# PiHatV2.net
KiCad netlist of a schematic drawn in EAGLE
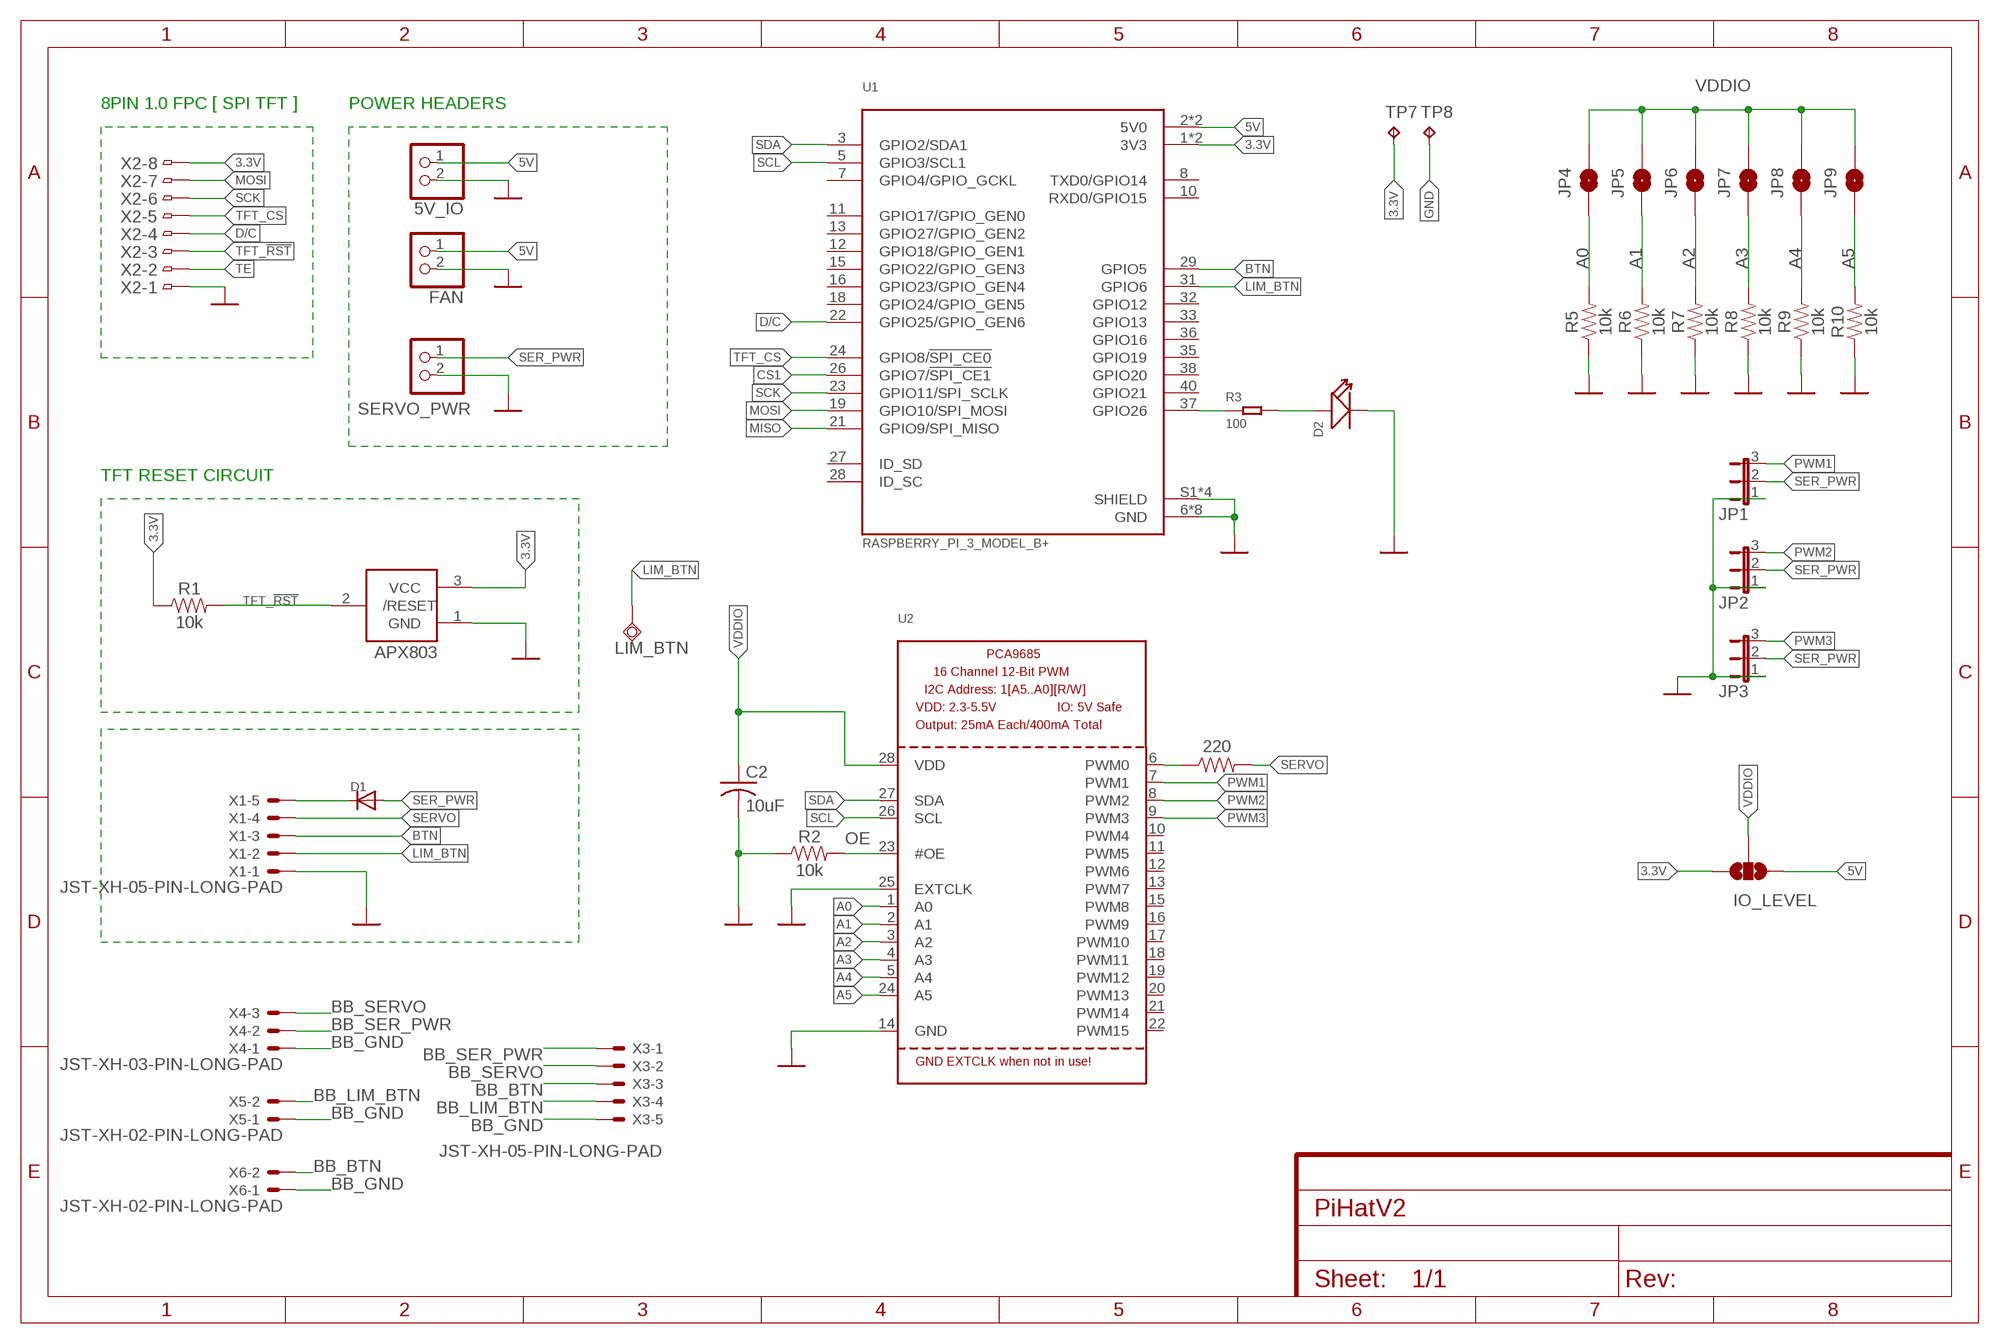
[diagram p0: schematic, sheet 1]

(export (version "E")
  (design (tool "Eeschema 10.0.6"))
  (components
    (comp (ref "5V_IO")
      (value "ONBOARDCONTROLINTERFACE_LED-BADGE_SCHEMATIC_ADAFRUIT_JST_2PIN-SMT-RA")
      (footprint "eagle-import:ONBOARDCONTROLINTERFACE_LED-BADGE_SCHEMATIC_ADAFRUIT_JST-PH-2-SMT-RA")
      (libsource (lib "eagle-import") (part "ONBOARDCONTROLINTERFACE_LED-BADGE_SCHEMATIC_ADAFRUIT_JST_2PIN-SMT-RA"))
    )
    (comp (ref "APX803")
      (value "ADAFRUIT_AXP083-SAG")
      (footprint "eagle-import:ADAFRUIT_SOT23")
      (libsource (lib "eagle-import") (part "ADAFRUIT_AXP083-SAG"))
    )
    (comp (ref "C2")
      (value "10uF")
      (footprint "eagle-import:C0805K")
      (libsource (lib "eagle-import") (part "C-USC0805K"))
    )
    (comp (ref "D1")
      (value "DIODESMA")
      (footprint "eagle-import:SMADIODE")
      (libsource (lib "eagle-import") (part "DIODESMA"))
    )
    (comp (ref "D2")
      (value "BLUE-0603")
      (footprint "eagle-import:LED-0603")
      (fields (field (name "MPN") "19-217-BHC-ZL1M2RY-3T"))
      (libsource (lib "eagle-import") (part "SMD-LED-CLEAR-BLUE(0603)"))
    )
    (comp (ref "FAN")
      (value "ONBOARDCONTROLINTERFACE_LED-BADGE_SCHEMATIC_ADAFRUIT_JST_2PIN-SMT-RA")
      (footprint "eagle-import:ONBOARDCONTROLINTERFACE_LED-BADGE_SCHEMATIC_ADAFRUIT_JST-PH-2-SMT-RA")
      (libsource (lib "eagle-import") (part "ONBOARDCONTROLINTERFACE_LED-BADGE_SCHEMATIC_ADAFRUIT_JST_2PIN-SMT-RA"))
    )
    (comp (ref "IO_LEVEL")
      (value "JUMPER-SMT_3_NO_NO-SILK")
      (footprint "eagle-import:SMT-JUMPER_3_NO_NO-SILK")
      (libsource (lib "eagle-import") (part "JUMPER-SMT_3_NO_NO-SILK"))
    )
    (comp (ref "JP1")
      (value "LED-BADGE_SCHEMATIC_JUMPER_JP2E")
      (footprint "eagle-import:LED-BADGE_SCHEMATIC_JUMPER_JP2")
      (libsource (lib "eagle-import") (part "LED-BADGE_SCHEMATIC_JUMPER_JP2E"))
    )
    (comp (ref "JP2")
      (value "LED-BADGE_SCHEMATIC_JUMPER_JP2E")
      (footprint "eagle-import:LED-BADGE_SCHEMATIC_JUMPER_JP2")
      (libsource (lib "eagle-import") (part "LED-BADGE_SCHEMATIC_JUMPER_JP2E"))
    )
    (comp (ref "JP3")
      (value "LED-BADGE_SCHEMATIC_JUMPER_JP2E")
      (footprint "eagle-import:LED-BADGE_SCHEMATIC_JUMPER_JP2")
      (libsource (lib "eagle-import") (part "LED-BADGE_SCHEMATIC_JUMPER_JP2E"))
    )
    (comp (ref "JP4")
      (value "JUMPER-SMT_2_NO_NO-SILK")
      (footprint "eagle-import:SMT-JUMPER_2_NO_NO-SILK")
      (libsource (lib "eagle-import") (part "JUMPER-SMT_2_NO_NO-SILK"))
    )
    (comp (ref "JP5")
      (value "JUMPER-SMT_2_NO_NO-SILK")
      (footprint "eagle-import:SMT-JUMPER_2_NO_NO-SILK")
      (libsource (lib "eagle-import") (part "JUMPER-SMT_2_NO_NO-SILK"))
    )
    (comp (ref "JP6")
      (value "JUMPER-SMT_2_NO_NO-SILK")
      (footprint "eagle-import:SMT-JUMPER_2_NO_NO-SILK")
      (libsource (lib "eagle-import") (part "JUMPER-SMT_2_NO_NO-SILK"))
    )
    (comp (ref "JP7")
      (value "JUMPER-SMT_2_NO_NO-SILK")
      (footprint "eagle-import:SMT-JUMPER_2_NO_NO-SILK")
      (libsource (lib "eagle-import") (part "JUMPER-SMT_2_NO_NO-SILK"))
    )
    (comp (ref "JP8")
      (value "JUMPER-SMT_2_NO_NO-SILK")
      (footprint "eagle-import:SMT-JUMPER_2_NO_NO-SILK")
      (libsource (lib "eagle-import") (part "JUMPER-SMT_2_NO_NO-SILK"))
    )
    (comp (ref "JP9")
      (value "JUMPER-SMT_2_NO_NO-SILK")
      (footprint "eagle-import:SMT-JUMPER_2_NO_NO-SILK")
      (libsource (lib "eagle-import") (part "JUMPER-SMT_2_NO_NO-SILK"))
    )
    (comp (ref "LIM_BTN")
      (value "TESTPAD_TPSQB1,27")
      (footprint "eagle-import:TESTPAD_B1,27")
      (libsource (lib "eagle-import") (part "TESTPAD_TPSQB1,27"))
    )
    (comp (ref "R1")
      (value "10k")
      (footprint "eagle-import:ARDUINO_3V_TTL_INTERFACE_2_PI_SPARKFUN-RESISTORS_0603_1")
      (libsource (lib "eagle-import") (part "ARDUINO_3V_TTL_INTERFACE_2_PI_SPARKFUN-RESISTORS_10KOHM-0603-1/10W-1%"))
    )
    (comp (ref "R2")
      (value "10k")
      (footprint "eagle-import:ARDUINO_3V_TTL_INTERFACE_2_PI_SPARKFUN-RESISTORS_0603_1")
      (libsource (lib "eagle-import") (part "ARDUINO_3V_TTL_INTERFACE_2_PI_SPARKFUN-RESISTORS_10KOHM-0603-1/10W-1%"))
    )
    (comp (ref "R3")
      (value "100")
      (footprint "eagle-import:R0805")
      (fields (field (name "MPN") "RC0805JR-071KL"))
      (libsource (lib "eagle-import") (part "SMD-RES-1K-5%-1/8W(0805)"))
    )
    (comp (ref "R4")
      (value "220")
      (footprint "eagle-import:ARDUINO_3V_TTL_INTERFACE_2_PI_SPARKFUN-RESISTORS_0603_1")
      (libsource (lib "eagle-import") (part "ARDUINO_3V_TTL_INTERFACE_2_PI_SPARKFUN-RESISTORS_10KOHM-0603-1/10W-1%"))
    )
    (comp (ref "R5")
      (value "10k")
      (footprint "eagle-import:ARDUINO_3V_TTL_INTERFACE_2_PI_SPARKFUN-RESISTORS_0603_1")
      (libsource (lib "eagle-import") (part "ARDUINO_3V_TTL_INTERFACE_2_PI_SPARKFUN-RESISTORS_10KOHM-0603-1/10W-1%"))
    )
    (comp (ref "R6")
      (value "10k")
      (footprint "eagle-import:ARDUINO_3V_TTL_INTERFACE_2_PI_SPARKFUN-RESISTORS_0603_1")
      (libsource (lib "eagle-import") (part "ARDUINO_3V_TTL_INTERFACE_2_PI_SPARKFUN-RESISTORS_10KOHM-0603-1/10W-1%"))
    )
    (comp (ref "R7")
      (value "10k")
      (footprint "eagle-import:ARDUINO_3V_TTL_INTERFACE_2_PI_SPARKFUN-RESISTORS_0603_1")
      (libsource (lib "eagle-import") (part "ARDUINO_3V_TTL_INTERFACE_2_PI_SPARKFUN-RESISTORS_10KOHM-0603-1/10W-1%"))
    )
    (comp (ref "R8")
      (value "10k")
      (footprint "eagle-import:ARDUINO_3V_TTL_INTERFACE_2_PI_SPARKFUN-RESISTORS_0603_1")
      (libsource (lib "eagle-import") (part "ARDUINO_3V_TTL_INTERFACE_2_PI_SPARKFUN-RESISTORS_10KOHM-0603-1/10W-1%"))
    )
    (comp (ref "R9")
      (value "10k")
      (footprint "eagle-import:ARDUINO_3V_TTL_INTERFACE_2_PI_SPARKFUN-RESISTORS_0603_1")
      (libsource (lib "eagle-import") (part "ARDUINO_3V_TTL_INTERFACE_2_PI_SPARKFUN-RESISTORS_10KOHM-0603-1/10W-1%"))
    )
    (comp (ref "R10")
      (value "10k")
      (footprint "eagle-import:ARDUINO_3V_TTL_INTERFACE_2_PI_SPARKFUN-RESISTORS_0603_1")
      (libsource (lib "eagle-import") (part "ARDUINO_3V_TTL_INTERFACE_2_PI_SPARKFUN-RESISTORS_10KOHM-0603-1/10W-1%"))
    )
    (comp (ref "SERVO_PWR")
      (value "ONBOARDCONTROLINTERFACE_LED-BADGE_SCHEMATIC_ADAFRUIT_JST_2PIN-SMT-RA")
      (footprint "eagle-import:ONBOARDCONTROLINTERFACE_LED-BADGE_SCHEMATIC_ADAFRUIT_JST-PH-2-SMT-RA")
      (libsource (lib "eagle-import") (part "ONBOARDCONTROLINTERFACE_LED-BADGE_SCHEMATIC_ADAFRUIT_JST_2PIN-SMT-RA"))
    )
    (comp (ref "TP7")
      (value "TPB2,54")
      (footprint "eagle-import:B2,54")
      (libsource (lib "eagle-import") (part "TPB2,54"))
    )
    (comp (ref "TP8")
      (value "TPB2,54")
      (footprint "eagle-import:B2,54")
      (libsource (lib "eagle-import") (part "TPB2,54"))
    )
    (comp (ref "U1")
      (value "RASPBERRY_PI_3_MODEL_B+")
      (footprint "eagle-import:MODULE_RASPBERRY_PI_3_MODEL_B+")
      (fields (field (name "MF") "Raspberry Pi") (field (name "MP") "RASPBERRY PI 3 MODEL B+"))
      (libsource (lib "eagle-import") (part "RASPBERRY_PI_3_MODEL_B+"))
    )
    (comp (ref "U2")
      (value "PCA9685")
      (footprint "eagle-import:TSSOP28")
      (libsource (lib "eagle-import") (part "PCA9685"))
    )
    (comp (ref "X1")
      (value "JST-XH-05-PIN-LONG-PAD")
      (footprint "eagle-import:JST-XH-05-PACKAGE-LONG-PAD")
      (libsource (lib "eagle-import") (part "JST-XH-05-PIN-LONG-PAD"))
    )
    (comp (ref "X2")
      (value "SCREENBREAKOUT_SCREENBREAKOUT_LEDMATRIXFPCCONNECTOR_CON-HIROSE_FH12-08S-1SH")
      (footprint "eagle-import:SCREENBREAKOUT_SCREENBREAKOUT_LEDMATRIXFPCCONNECTOR_CON-HIROSE_FH12-08S-1SH")
      (libsource (lib "eagle-import") (part "SCREENBREAKOUT_SCREENBREAKOUT_LEDMATRIXFPCCONNECTOR_CON-HIROSE_FH12-08S-1SH"))
    )
    (comp (ref "X3")
      (value "JST-XH-05-PIN-LONG-PAD")
      (footprint "eagle-import:JST-XH-05-PACKAGE-LONG-PAD")
      (libsource (lib "eagle-import") (part "JST-XH-05-PIN-LONG-PAD"))
    )
    (comp (ref "X4")
      (value "JST-XH-03-PIN-LONG-PAD")
      (footprint "eagle-import:JST-XH-03-PACKAGE-LONG-PAD")
      (libsource (lib "eagle-import") (part "JST-XH-03-PIN-LONG-PAD"))
    )
    (comp (ref "X5")
      (value "JST-XH-02-PIN-LONG-PAD")
      (footprint "eagle-import:JST-XH-02-PACKAGE-LONG-PAD")
      (libsource (lib "eagle-import") (part "JST-XH-02-PIN-LONG-PAD"))
    )
    (comp (ref "X6")
      (value "JST-XH-02-PIN-LONG-PAD")
      (footprint "eagle-import:JST-XH-02-PACKAGE-LONG-PAD")
      (libsource (lib "eagle-import") (part "JST-XH-02-PIN-LONG-PAD"))
    )
  )
  (nets
    (net (code "1") (name "/BB_BTN") (class "Default")
      (node (ref "X3") (pin "3") (pinfunction "S_3") (pintype "passive"))
      (node (ref "X6") (pin "2") (pinfunction "S_2") (pintype "passive"))
    )
    (net (code "2") (name "/BB_GND") (class "Default")
      (node (ref "X3") (pin "5") (pinfunction "S_5") (pintype "passive"))
      (node (ref "X4") (pin "1") (pinfunction "S_1") (pintype "passive"))
      (node (ref "X5") (pin "1") (pinfunction "S_1") (pintype "passive"))
      (node (ref "X6") (pin "1") (pinfunction "S_1") (pintype "passive"))
    )
    (net (code "3") (name "/BB_LIM_BTN") (class "Default")
      (node (ref "X3") (pin "4") (pinfunction "S_4") (pintype "passive"))
      (node (ref "X5") (pin "2") (pinfunction "S_2") (pintype "passive"))
    )
    (net (code "4") (name "/BB_SERVO") (class "Default")
      (node (ref "X3") (pin "2") (pinfunction "S_2") (pintype "passive"))
      (node (ref "X4") (pin "3") (pinfunction "S_3") (pintype "passive"))
    )
    (net (code "5") (name "/BB_SER_PWR") (class "Default")
      (node (ref "X3") (pin "1") (pinfunction "S_1") (pintype "passive"))
      (node (ref "X4") (pin "2") (pinfunction "S_2") (pintype "passive"))
    )
    (net (code "6") (name "/OE") (class "Default")
      (node (ref "R2") (pin "2") (pinfunction "2_2") (pintype "passive"))
      (node (ref "U2") (pin "23") (pinfunction "#OE_23") (pintype "input"))
    )
    (net (code "7") (name "/TFT_~{RST}") (class "Default")
      (node (ref "APX803") (pin "2") (pinfunction "/RESET_2") (pintype "output"))
      (node (ref "R1") (pin "2") (pinfunction "2_2") (pintype "passive"))
      (node (ref "X2") (pin "3") (pinfunction "1_3") (pintype "passive"))
    )
    (net (code "8") (name "3.3V") (class "Default")
      (node (ref "APX803") (pin "3") (pinfunction "VCC_3") (pintype "power_in"))
      (node (ref "IO_LEVEL") (pin "3") (pinfunction "3_3") (pintype "passive"))
      (node (ref "R1") (pin "1") (pinfunction "1_1") (pintype "passive"))
      (node (ref "TP7") (pin "TP") (pinfunction "TP_TP") (pintype "input"))
      (node (ref "U1") (pin "1") (pinfunction "3V3_1") (pintype "power_in"))
      (node (ref "U1") (pin "17") (pinfunction "3V3_17") (pintype "power_in"))
      (node (ref "X2") (pin "8") (pinfunction "1_8") (pintype "passive"))
    )
    (net (code "9") (name "5V") (class "Default")
      (node (ref "5V_IO") (pin "1") (pinfunction "2_1") (pintype "passive"))
      (node (ref "FAN") (pin "1") (pinfunction "2_1") (pintype "passive"))
      (node (ref "IO_LEVEL") (pin "1") (pinfunction "1_1") (pintype "passive"))
      (node (ref "U1") (pin "2") (pinfunction "5V0_2") (pintype "power_in"))
      (node (ref "U1") (pin "4") (pinfunction "5V0_4") (pintype "power_in"))
    )
    (net (code "10") (name "A0") (class "Default")
      (node (ref "JP4") (pin "1") (pinfunction "1_1") (pintype "passive"))
      (node (ref "R5") (pin "2") (pinfunction "2_2") (pintype "passive"))
      (node (ref "U2") (pin "1") (pinfunction "A0_1") (pintype "bidirectional"))
    )
    (net (code "11") (name "A1") (class "Default")
      (node (ref "JP5") (pin "1") (pinfunction "1_1") (pintype "passive"))
      (node (ref "R6") (pin "2") (pinfunction "2_2") (pintype "passive"))
      (node (ref "U2") (pin "2") (pinfunction "A1_2") (pintype "bidirectional"))
    )
    (net (code "12") (name "A2") (class "Default")
      (node (ref "JP6") (pin "1") (pinfunction "1_1") (pintype "passive"))
      (node (ref "R7") (pin "2") (pinfunction "2_2") (pintype "passive"))
      (node (ref "U2") (pin "3") (pinfunction "A2_3") (pintype "bidirectional"))
    )
    (net (code "13") (name "A3") (class "Default")
      (node (ref "JP7") (pin "1") (pinfunction "1_1") (pintype "passive"))
      (node (ref "R8") (pin "2") (pinfunction "2_2") (pintype "passive"))
      (node (ref "U2") (pin "4") (pinfunction "A3_4") (pintype "bidirectional"))
    )
    (net (code "14") (name "A4") (class "Default")
      (node (ref "JP8") (pin "1") (pinfunction "1_1") (pintype "passive"))
      (node (ref "R9") (pin "2") (pinfunction "2_2") (pintype "passive"))
      (node (ref "U2") (pin "5") (pinfunction "A4_5") (pintype "bidirectional"))
    )
    (net (code "15") (name "A5") (class "Default")
      (node (ref "JP9") (pin "1") (pinfunction "1_1") (pintype "passive"))
      (node (ref "R10") (pin "2") (pinfunction "2_2") (pintype "passive"))
      (node (ref "U2") (pin "24") (pinfunction "A5_24") (pintype "bidirectional"))
    )
    (net (code "16") (name "BTN") (class "Default")
      (node (ref "U1") (pin "29") (pinfunction "GPIO5_29") (pintype "bidirectional"))
      (node (ref "X1") (pin "3") (pinfunction "S_3") (pintype "passive"))
    )
    (net (code "17") (name "CS1") (class "Default")
      (node (ref "U1") (pin "26") (pinfunction "GPIO7/~{SPI_CE1}_26") (pintype "bidirectional"))
    )
    (net (code "18") (name "D{slash}C") (class "Default")
      (node (ref "U1") (pin "22") (pinfunction "GPIO25/GPIO_GEN6_22") (pintype "bidirectional"))
      (node (ref "X2") (pin "4") (pinfunction "1_4") (pintype "passive"))
    )
    (net (code "19") (name "GND") (class "Default")
      (node (ref "5V_IO") (pin "2") (pinfunction "1_2") (pintype "passive"))
      (node (ref "APX803") (pin "1") (pinfunction "GND_1") (pintype "power_in"))
      (node (ref "C2") (pin "2") (pinfunction "2_2") (pintype "passive"))
      (node (ref "D2") (pin "-") (pinfunction "-_-") (pintype "passive"))
      (node (ref "FAN") (pin "2") (pinfunction "1_2") (pintype "passive"))
      (node (ref "JP1") (pin "1") (pinfunction "1_1") (pintype "passive"))
      (node (ref "JP2") (pin "1") (pinfunction "1_1") (pintype "passive"))
      (node (ref "JP3") (pin "1") (pinfunction "1_1") (pintype "passive"))
      (node (ref "R10") (pin "1") (pinfunction "1_1") (pintype "passive"))
      (node (ref "R2") (pin "1") (pinfunction "1_1") (pintype "passive"))
      (node (ref "R5") (pin "1") (pinfunction "1_1") (pintype "passive"))
      (node (ref "R6") (pin "1") (pinfunction "1_1") (pintype "passive"))
      (node (ref "R7") (pin "1") (pinfunction "1_1") (pintype "passive"))
      (node (ref "R8") (pin "1") (pinfunction "1_1") (pintype "passive"))
      (node (ref "R9") (pin "1") (pinfunction "1_1") (pintype "passive"))
      (node (ref "SERVO_PWR") (pin "2") (pinfunction "1_2") (pintype "passive"))
      (node (ref "TP8") (pin "TP") (pinfunction "TP_TP") (pintype "input"))
      (node (ref "U1") (pin "14") (pinfunction "GND_14") (pintype "power_in"))
      (node (ref "U1") (pin "20") (pinfunction "GND_20") (pintype "power_in"))
      (node (ref "U1") (pin "25") (pinfunction "GND_25") (pintype "power_in"))
      (node (ref "U1") (pin "30") (pinfunction "GND_30") (pintype "power_in"))
      (node (ref "U1") (pin "34") (pinfunction "GND_34") (pintype "power_in"))
      (node (ref "U1") (pin "39") (pinfunction "GND_39") (pintype "power_in"))
      (node (ref "U1") (pin "6") (pinfunction "GND_6") (pintype "power_in"))
      (node (ref "U1") (pin "9") (pinfunction "GND_9") (pintype "power_in"))
      (node (ref "U1") (pin "S1") (pinfunction "SHIELD_S1") (pintype "power_in"))
      (node (ref "U1") (pin "S2") (pinfunction "SHIELD_S2") (pintype "power_in"))
      (node (ref "U1") (pin "S3") (pinfunction "SHIELD_S3") (pintype "power_in"))
      (node (ref "U1") (pin "S4") (pinfunction "SHIELD_S4") (pintype "power_in"))
      (node (ref "U2") (pin "14") (pinfunction "GND_14") (pintype "power_in"))
      (node (ref "U2") (pin "25") (pinfunction "EXTCLK_25") (pintype "input"))
      (node (ref "X1") (pin "1") (pinfunction "S_1") (pintype "passive"))
      (node (ref "X2") (pin "1") (pinfunction "1_1") (pintype "passive"))
    )
    (net (code "20") (name "LIM_BTN") (class "Default")
      (node (ref "LIM_BTN") (pin "TP") (pinfunction "TP_TP") (pintype "input"))
      (node (ref "U1") (pin "31") (pinfunction "GPIO6_31") (pintype "bidirectional"))
      (node (ref "X1") (pin "2") (pinfunction "S_2") (pintype "passive"))
    )
    (net (code "21") (name "MISO") (class "Default")
      (node (ref "U1") (pin "21") (pinfunction "GPIO9/SPI_MISO_21") (pintype "bidirectional"))
    )
    (net (code "22") (name "MOSI") (class "Default")
      (node (ref "U1") (pin "19") (pinfunction "GPIO10/SPI_MOSI_19") (pintype "bidirectional"))
      (node (ref "X2") (pin "7") (pinfunction "1_7") (pintype "passive"))
    )
    (net (code "23") (name "Net-(D2-Pad+)") (class "Default")
      (node (ref "D2") (pin "+") (pinfunction "+_+") (pintype "passive"))
      (node (ref "R3") (pin "2") (pinfunction "2_2") (pintype "passive"))
    )
    (net (code "24") (name "Net-(U1-GPIO26)") (class "Default")
      (node (ref "R3") (pin "1") (pinfunction "1_1") (pintype "passive"))
      (node (ref "U1") (pin "37") (pinfunction "GPIO26_37") (pintype "bidirectional"))
    )
    (net (code "25") (name "Net-(U2-PWM0)") (class "Default")
      (node (ref "R4") (pin "1") (pinfunction "1_1") (pintype "passive"))
      (node (ref "U2") (pin "6") (pinfunction "PWM0_6") (pintype "output"))
    )
    (net (code "26") (name "Net-(X1E-S)") (class "Default")
      (node (ref "D1") (pin "C") (pinfunction "C_C") (pintype "passive"))
      (node (ref "X1") (pin "5") (pinfunction "S_5") (pintype "passive"))
    )
    (net (code "27") (name "PWM1") (class "Default")
      (node (ref "JP1") (pin "3") (pinfunction "3_3") (pintype "passive"))
      (node (ref "U2") (pin "7") (pinfunction "PWM1_7") (pintype "output"))
    )
    (net (code "28") (name "PWM2") (class "Default")
      (node (ref "JP2") (pin "3") (pinfunction "3_3") (pintype "passive"))
      (node (ref "U2") (pin "8") (pinfunction "PWM2_8") (pintype "output"))
    )
    (net (code "29") (name "PWM3") (class "Default")
      (node (ref "JP3") (pin "3") (pinfunction "3_3") (pintype "passive"))
      (node (ref "U2") (pin "9") (pinfunction "PWM3_9") (pintype "output"))
    )
    (net (code "30") (name "SCK") (class "Default")
      (node (ref "U1") (pin "23") (pinfunction "GPIO11/SPI_SCLK_23") (pintype "bidirectional"))
      (node (ref "X2") (pin "6") (pinfunction "1_6") (pintype "passive"))
    )
    (net (code "31") (name "SCL") (class "Default")
      (node (ref "U1") (pin "5") (pinfunction "GPIO3/SCL1_5") (pintype "bidirectional"))
      (node (ref "U2") (pin "26") (pinfunction "SCL_26") (pintype "bidirectional"))
    )
    (net (code "32") (name "SDA") (class "Default")
      (node (ref "U1") (pin "3") (pinfunction "GPIO2/SDA1_3") (pintype "bidirectional"))
      (node (ref "U2") (pin "27") (pinfunction "SDA_27") (pintype "bidirectional"))
    )
    (net (code "33") (name "SERVO") (class "Default")
      (node (ref "R4") (pin "2") (pinfunction "2_2") (pintype "passive"))
      (node (ref "X1") (pin "4") (pinfunction "S_4") (pintype "passive"))
    )
    (net (code "34") (name "SER_PWR") (class "Default")
      (node (ref "D1") (pin "A") (pinfunction "A_A") (pintype "passive"))
      (node (ref "JP1") (pin "2") (pinfunction "2_2") (pintype "passive"))
      (node (ref "JP2") (pin "2") (pinfunction "2_2") (pintype "passive"))
      (node (ref "JP3") (pin "2") (pinfunction "2_2") (pintype "passive"))
      (node (ref "SERVO_PWR") (pin "1") (pinfunction "2_1") (pintype "passive"))
    )
    (net (code "35") (name "TE") (class "Default")
      (node (ref "X2") (pin "2") (pinfunction "1_2") (pintype "passive"))
    )
    (net (code "36") (name "TFT_CS") (class "Default")
      (node (ref "U1") (pin "24") (pinfunction "GPIO8/~{SPI_CE0}_24") (pintype "bidirectional"))
      (node (ref "X2") (pin "5") (pinfunction "1_5") (pintype "passive"))
    )
    (net (code "37") (name "VDDIO") (class "Default")
      (node (ref "C2") (pin "1") (pinfunction "1_1") (pintype "passive"))
      (node (ref "IO_LEVEL") (pin "2") (pinfunction "2_2") (pintype "passive"))
      (node (ref "JP4") (pin "2") (pinfunction "2_2") (pintype "passive"))
      (node (ref "JP5") (pin "2") (pinfunction "2_2") (pintype "passive"))
      (node (ref "JP6") (pin "2") (pinfunction "2_2") (pintype "passive"))
      (node (ref "JP7") (pin "2") (pinfunction "2_2") (pintype "passive"))
      (node (ref "JP8") (pin "2") (pinfunction "2_2") (pintype "passive"))
      (node (ref "JP9") (pin "2") (pinfunction "2_2") (pintype "passive"))
      (node (ref "U2") (pin "28") (pinfunction "VDD_28") (pintype "power_in"))
    )
    (net (code "38") (name "unconnected-(U1-GPIO4{slash}GPIO_GCKL-Pad7)") (class "Default")
      (node (ref "U1") (pin "7") (pinfunction "GPIO4/GPIO_GCKL_7") (pintype "bidirectional"))
    )
    (net (code "39") (name "unconnected-(U1-GPIO12-Pad32)") (class "Default")
      (node (ref "U1") (pin "32") (pinfunction "GPIO12_32") (pintype "bidirectional"))
    )
    (net (code "40") (name "unconnected-(U1-GPIO13-Pad33)") (class "Default")
      (node (ref "U1") (pin "33") (pinfunction "GPIO13_33") (pintype "bidirectional"))
    )
    (net (code "41") (name "unconnected-(U1-GPIO16-Pad36)") (class "Default")
      (node (ref "U1") (pin "36") (pinfunction "GPIO16_36") (pintype "bidirectional"))
    )
    (net (code "42") (name "unconnected-(U1-GPIO17{slash}GPIO_GEN0-Pad11)") (class "Default")
      (node (ref "U1") (pin "11") (pinfunction "GPIO17/GPIO_GEN0_11") (pintype "bidirectional"))
    )
    (net (code "43") (name "unconnected-(U1-GPIO18{slash}GPIO_GEN1-Pad12)") (class "Default")
      (node (ref "U1") (pin "12") (pinfunction "GPIO18/GPIO_GEN1_12") (pintype "bidirectional"))
    )
    (net (code "44") (name "unconnected-(U1-GPIO19-Pad35)") (class "Default")
      (node (ref "U1") (pin "35") (pinfunction "GPIO19_35") (pintype "bidirectional"))
    )
    (net (code "45") (name "unconnected-(U1-GPIO20-Pad38)") (class "Default")
      (node (ref "U1") (pin "38") (pinfunction "GPIO20_38") (pintype "bidirectional"))
    )
    (net (code "46") (name "unconnected-(U1-GPIO21-Pad40)") (class "Default")
      (node (ref "U1") (pin "40") (pinfunction "GPIO21_40") (pintype "bidirectional"))
    )
    (net (code "47") (name "unconnected-(U1-GPIO22{slash}GPIO_GEN3-Pad15)") (class "Default")
      (node (ref "U1") (pin "15") (pinfunction "GPIO22/GPIO_GEN3_15") (pintype "bidirectional"))
    )
    (net (code "48") (name "unconnected-(U1-GPIO23{slash}GPIO_GEN4-Pad16)") (class "Default")
      (node (ref "U1") (pin "16") (pinfunction "GPIO23/GPIO_GEN4_16") (pintype "bidirectional"))
    )
    (net (code "49") (name "unconnected-(U1-GPIO24{slash}GPIO_GEN5-Pad18)") (class "Default")
      (node (ref "U1") (pin "18") (pinfunction "GPIO24/GPIO_GEN5_18") (pintype "bidirectional"))
    )
    (net (code "50") (name "unconnected-(U1-GPIO27{slash}GPIO_GEN2-Pad13)") (class "Default")
      (node (ref "U1") (pin "13") (pinfunction "GPIO27/GPIO_GEN2_13") (pintype "bidirectional"))
    )
    (net (code "51") (name "unconnected-(U1-ID_SC-Pad28)") (class "Default")
      (node (ref "U1") (pin "28") (pinfunction "ID_SC_28") (pintype "bidirectional"))
    )
    (net (code "52") (name "unconnected-(U1-ID_SD-Pad27)") (class "Default")
      (node (ref "U1") (pin "27") (pinfunction "ID_SD_27") (pintype "bidirectional"))
    )
    (net (code "53") (name "unconnected-(U1-RXD0{slash}GPIO15-Pad10)") (class "Default")
      (node (ref "U1") (pin "10") (pinfunction "RXD0/GPIO15_10") (pintype "bidirectional"))
    )
    (net (code "54") (name "unconnected-(U1-TXD0{slash}GPIO14-Pad8)") (class "Default")
      (node (ref "U1") (pin "8") (pinfunction "TXD0/GPIO14_8") (pintype "bidirectional"))
    )
    (net (code "55") (name "unconnected-(U2-PWM4-Pad10)") (class "Default")
      (node (ref "U2") (pin "10") (pinfunction "PWM4_10") (pintype "output"))
    )
    (net (code "56") (name "unconnected-(U2-PWM5-Pad11)") (class "Default")
      (node (ref "U2") (pin "11") (pinfunction "PWM5_11") (pintype "output"))
    )
    (net (code "57") (name "unconnected-(U2-PWM6-Pad12)") (class "Default")
      (node (ref "U2") (pin "12") (pinfunction "PWM6_12") (pintype "output"))
    )
    (net (code "58") (name "unconnected-(U2-PWM7-Pad13)") (class "Default")
      (node (ref "U2") (pin "13") (pinfunction "PWM7_13") (pintype "output"))
    )
    (net (code "59") (name "unconnected-(U2-PWM8-Pad15)") (class "Default")
      (node (ref "U2") (pin "15") (pinfunction "PWM8_15") (pintype "output"))
    )
    (net (code "60") (name "unconnected-(U2-PWM9-Pad16)") (class "Default")
      (node (ref "U2") (pin "16") (pinfunction "PWM9_16") (pintype "output"))
    )
    (net (code "61") (name "unconnected-(U2-PWM10-Pad17)") (class "Default")
      (node (ref "U2") (pin "17") (pinfunction "PWM10_17") (pintype "output"))
    )
    (net (code "62") (name "unconnected-(U2-PWM11-Pad18)") (class "Default")
      (node (ref "U2") (pin "18") (pinfunction "PWM11_18") (pintype "output"))
    )
    (net (code "63") (name "unconnected-(U2-PWM12-Pad19)") (class "Default")
      (node (ref "U2") (pin "19") (pinfunction "PWM12_19") (pintype "output"))
    )
    (net (code "64") (name "unconnected-(U2-PWM13-Pad20)") (class "Default")
      (node (ref "U2") (pin "20") (pinfunction "PWM13_20") (pintype "output"))
    )
    (net (code "65") (name "unconnected-(U2-PWM14-Pad21)") (class "Default")
      (node (ref "U2") (pin "21") (pinfunction "PWM14_21") (pintype "output"))
    )
    (net (code "66") (name "unconnected-(U2-PWM15-Pad22)") (class "Default")
      (node (ref "U2") (pin "22") (pinfunction "PWM15_22") (pintype "output"))
    )
  )
)
